# 05_Display.net
KiCad netlist of a schematic drawn in Altium Designer
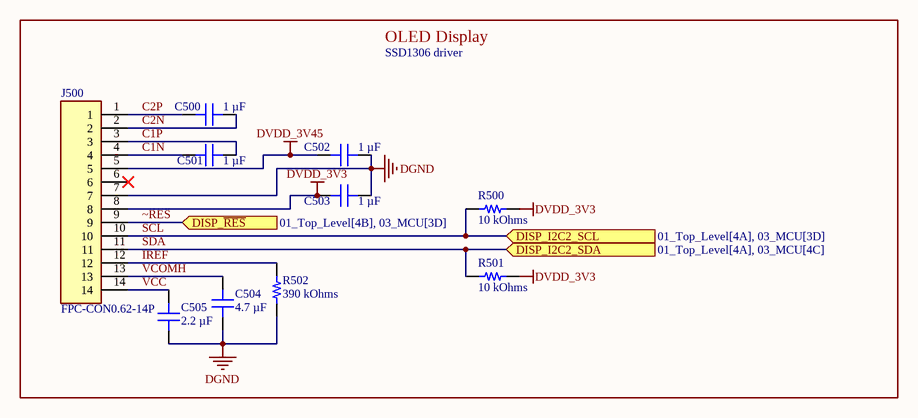
[diagram p0: 05_Display.SchDoc]

(export (version "E")
  (design (tool "Eeschema 10.0.6"))
  (components
    (comp (ref "C500")
      (value "1 µF")
      (footprint "CAP 0603_1608")
      (description "CAP CER 1UF 25V X5R 0603")
      (fields
        (field (name "PART NUMBER") "CL10A105KA8NFNC")
        (field (name "CAPACITANCE") "1 µF")
        (field (name "MANUFACTURER") "Samsung Electro-Mechanics")
      )
      (libsource (lib "Celestial Altium Library - altium_library") (part "Capacitor"))
    )
    (comp (ref "C501")
      (value "1 µF")
      (footprint "CAP 0603_1608")
      (description "CAP CER 1UF 25V X5R 0603")
      (fields
        (field (name "PART NUMBER") "CL10A105KA8NFNC")
        (field (name "CAPACITANCE") "1 µF")
        (field (name "MANUFACTURER") "Samsung Electro-Mechanics")
      )
      (libsource (lib "Celestial Altium Library - altium_library") (part "Capacitor"))
    )
    (comp (ref "C502")
      (value "1 µF")
      (footprint "CAP 0603_1608")
      (description "CAP CER 1UF 25V X5R 0603")
      (fields
        (field (name "PART NUMBER") "CL10A105KA8NFNC")
        (field (name "CAPACITANCE") "1 µF")
        (field (name "MANUFACTURER") "Samsung Electro-Mechanics")
      )
      (libsource (lib "Celestial Altium Library - altium_library") (part "Capacitor"))
    )
    (comp (ref "C503")
      (value "1 µF")
      (footprint "CAP 0603_1608")
      (description "CAP CER 1UF 25V X5R 0603")
      (fields
        (field (name "PART NUMBER") "CL10A105KA8NFNC")
        (field (name "CAPACITANCE") "1 µF")
        (field (name "MANUFACTURER") "Samsung Electro-Mechanics")
      )
      (libsource (lib "Celestial Altium Library - altium_library") (part "Capacitor"))
    )
    (comp (ref "C504")
      (value "4.7 µF")
      (footprint "CAP 0805_2012")
      (description "CAP CER 4.7UF 25V X5R 0805")
      (fields
        (field (name "PART NUMBER") "MSAST21GAB5475KTNA01")
        (field (name "CAPACITANCE") "4.7 µF")
        (field (name "MANUFACTURER") "Taiyo Yuden")
      )
      (libsource (lib "Celestial Altium Library - altium_library") (part "Capacitor"))
    )
    (comp (ref "C505")
      (value "2.2 µF")
      (footprint "CAP 0603_1608")
      (description "CAP CER 2.2UF 25V X5R 0603")
      (fields
        (field (name "PART NUMBER") "GRM188R61E225KA12D")
        (field (name "CAPACITANCE") "2.2 µF")
        (field (name "MANUFACTURER") "Murata Electronics")
      )
      (libsource (lib "Celestial Altium Library - altium_library") (part "Capacitor"))
    )
    (comp (ref "J500")
      (value "FPC-CON0.62-14P")
      (footprint "FPC-CON0.62-14P")
      (description "FPC Connector 14 Pin 0.62mm Pitch")
      (libsource (lib "P3_MP3_Player") (part "FPC-CON0.62-14P"))
    )
    (comp (ref "R500")
      (value "10 kOhms")
      (footprint "RES 0402_1005")
      (description "RES SMD 10K OHM 1% 1/16W 0402")
      (fields (field (name "PART NUMBER") "CRCW040210K0FKEE") (field (name "MANUFACTURER") "Vishay Dale"))
      (libsource (lib "Celestial Altium Library - altium_library") (part "Resistor"))
    )
    (comp (ref "R501")
      (value "10 kOhms")
      (footprint "RES 0402_1005")
      (description "RES SMD 10K OHM 1% 1/16W 0402")
      (fields (field (name "PART NUMBER") "CRCW040210K0FKEE") (field (name "MANUFACTURER") "Vishay Dale"))
      (libsource (lib "Celestial Altium Library - altium_library") (part "Resistor"))
    )
    (comp (ref "R502")
      (value "390 kOhms")
      (footprint "RES 0402_1005")
      (description "RES 390K OHM 1% 1/16W 0402")
      (fields
        (field (name "PART NUMBER") "CRGCQ0402F390K")
        (field (name "MANUFACTURER") "TE Connectivity Passive Product")
      )
      (libsource (lib "Celestial Altium Library - altium_library") (part "Resistor"))
    )
  )
  (nets
    (net (code "1") (name "/C1N") (class "Default")
      (node (ref "C501") (pin "1") (pinfunction "1_1") (pintype "passive"))
      (node (ref "J500") (pin "4") (pinfunction "4_4") (pintype "passive"))
    )
    (net (code "2") (name "/C1P") (class "Default")
      (node (ref "C501") (pin "2") (pinfunction "2_2") (pintype "passive"))
      (node (ref "J500") (pin "3") (pinfunction "3_3") (pintype "passive"))
    )
    (net (code "3") (name "/C2N") (class "Default")
      (node (ref "C500") (pin "2") (pinfunction "2_2") (pintype "passive"))
      (node (ref "J500") (pin "2") (pinfunction "2_2") (pintype "passive"))
    )
    (net (code "4") (name "/C2P") (class "Default")
      (node (ref "C500") (pin "1") (pinfunction "1_1") (pintype "passive"))
      (node (ref "J500") (pin "1") (pinfunction "1_1") (pintype "passive"))
    )
    (net (code "5") (name "/IREF") (class "Default")
      (node (ref "J500") (pin "12") (pinfunction "12_12") (pintype "passive"))
      (node (ref "R502") (pin "2") (pinfunction "2_2") (pintype "passive"))
    )
    (net (code "6") (name "/SCL") (class "Default")
      (node (ref "J500") (pin "10") (pinfunction "10_10") (pintype "passive"))
      (node (ref "R500") (pin "2") (pinfunction "2_2") (pintype "passive"))
    )
    (net (code "7") (name "/SDA") (class "Default")
      (node (ref "J500") (pin "11") (pinfunction "11_11") (pintype "passive"))
      (node (ref "R501") (pin "2") (pinfunction "2_2") (pintype "passive"))
    )
    (net (code "8") (name "/VCC") (class "Default")
      (node (ref "C505") (pin "1") (pinfunction "1_1") (pintype "passive"))
      (node (ref "J500") (pin "14") (pinfunction "14_14") (pintype "passive"))
    )
    (net (code "9") (name "/VCOMH") (class "Default")
      (node (ref "C504") (pin "2") (pinfunction "2_2") (pintype "passive"))
      (node (ref "J500") (pin "13") (pinfunction "13_13") (pintype "passive"))
    )
    (net (code "10") (name "/~RES") (class "Default")
      (node (ref "J500") (pin "9") (pinfunction "9_9") (pintype "passive"))
    )
    (net (code "11") (name "DGND") (class "Default")
      (node (ref "C502") (pin "2") (pinfunction "2_2") (pintype "passive"))
      (node (ref "C503") (pin "2") (pinfunction "2_2") (pintype "passive"))
      (node (ref "C504") (pin "1") (pinfunction "1_1") (pintype "passive"))
      (node (ref "C505") (pin "2") (pinfunction "2_2") (pintype "passive"))
      (node (ref "J500") (pin "7") (pinfunction "7_7") (pintype "passive"))
      (node (ref "R502") (pin "1") (pinfunction "1_1") (pintype "passive"))
    )
    (net (code "12") (name "DVDD_3V3") (class "Default")
      (node (ref "C503") (pin "1") (pinfunction "1_1") (pintype "passive"))
      (node (ref "J500") (pin "8") (pinfunction "8_8") (pintype "passive"))
      (node (ref "R500") (pin "1") (pinfunction "1_1") (pintype "passive"))
      (node (ref "R501") (pin "1") (pinfunction "1_1") (pintype "passive"))
    )
    (net (code "13") (name "DVDD_3V45") (class "Default")
      (node (ref "C502") (pin "1") (pinfunction "1_1") (pintype "passive"))
      (node (ref "J500") (pin "5") (pinfunction "5_5") (pintype "passive"))
    )
    (net (code "14") (name "unconnected-(J500-Pad6)") (class "Default")
      (node (ref "J500") (pin "6") (pinfunction "6_6") (pintype "passive+no_connect"))
    )
  )
)
